# BCK_REVA_3.net
KiCad netlist of a schematic drawn in Altium Designer
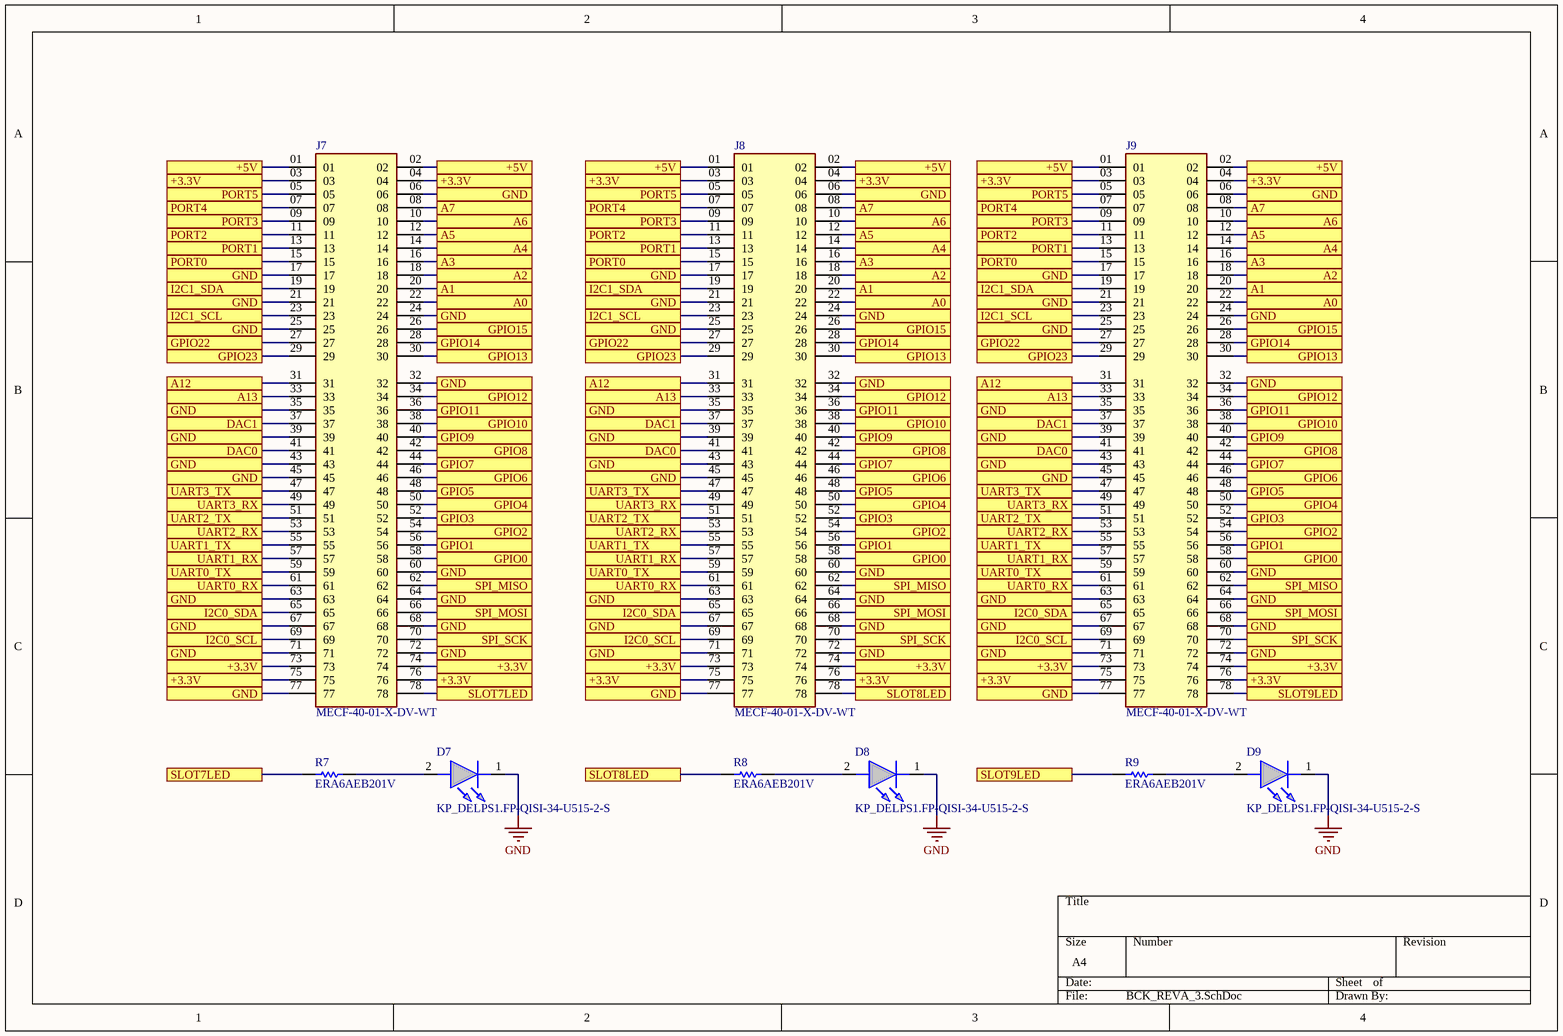
[diagram p0: BCK_REVA_3.SchDoc]

(export (version "E")
  (design (tool "Eeschema 10.0.6"))
  (components
    (comp (ref "D7")
      (value "KP_DELPS1.FP-QISI-34-U515-2-S")
      (footprint "KPDELPS1FPQISI34U5152S:KPDELPS1FPQISI34U5152S")
      (description "High Power LEDs - Single Color Pure Green TOPLED E1608")
      (fields
        (field (name "MANUFACTURER_PART_NUMBER") "KP DELPS1.FP-QISI-34-U515-2-S")
        (field (name "MOUSER PART NUMBER") "720-KPDELPS1FPA0817")
      )
      (libsource (lib "Backplane_REVA") (part "KP_DELPS1.FP-QISI-34-U515-2-S"))
    )
    (comp (ref "D8")
      (value "KP_DELPS1.FP-QISI-34-U515-2-S")
      (footprint "KPDELPS1FPQISI34U5152S:KPDELPS1FPQISI34U5152S")
      (description "High Power LEDs - Single Color Pure Green TOPLED E1608")
      (fields
        (field (name "MANUFACTURER_PART_NUMBER") "KP DELPS1.FP-QISI-34-U515-2-S")
        (field (name "MOUSER PART NUMBER") "720-KPDELPS1FPA0817")
      )
      (libsource (lib "Backplane_REVA") (part "KP_DELPS1.FP-QISI-34-U515-2-S"))
    )
    (comp (ref "D9")
      (value "KP_DELPS1.FP-QISI-34-U515-2-S")
      (footprint "KPDELPS1FPQISI34U5152S:KPDELPS1FPQISI34U5152S")
      (description "High Power LEDs - Single Color Pure Green TOPLED E1608")
      (fields
        (field (name "MANUFACTURER_PART_NUMBER") "KP DELPS1.FP-QISI-34-U515-2-S")
        (field (name "MOUSER PART NUMBER") "720-KPDELPS1FPA0817")
      )
      (libsource (lib "Backplane_REVA") (part "KP_DELPS1.FP-QISI-34-U515-2-S"))
    )
    (comp (ref "J7")
      (value "MECF-40-01-X-DV-WT")
      (footprint "SAMTEC_MECF-40-01-X-DV-WT:SAMTEC_MECF-40-01-X-DV-WT")
      (description "MECF .050\" EDGE CARD ASSEMBLY")
      (fields (field (name "MF") "Samtec"))
      (libsource (lib "Backplane_REVA") (part "MECF-40-01-X-DV-WT"))
    )
    (comp (ref "J8")
      (value "MECF-40-01-X-DV-WT")
      (footprint "SAMTEC_MECF-40-01-X-DV-WT:SAMTEC_MECF-40-01-X-DV-WT")
      (description "MECF .050\" EDGE CARD ASSEMBLY")
      (fields (field (name "MF") "Samtec"))
      (libsource (lib "Backplane_REVA") (part "MECF-40-01-X-DV-WT"))
    )
    (comp (ref "J9")
      (value "MECF-40-01-X-DV-WT")
      (footprint "SAMTEC_MECF-40-01-X-DV-WT:SAMTEC_MECF-40-01-X-DV-WT")
      (description "MECF .050\" EDGE CARD ASSEMBLY")
      (fields (field (name "MF") "Samtec"))
      (libsource (lib "Backplane_REVA") (part "MECF-40-01-X-DV-WT"))
    )
    (comp (ref "R7")
      (value "ERA6AEB201V")
      (footprint "RESC2013X60X40NL20T25")
      (fields (field (name "MANUFACTURER") "Panasonic"))
      (libsource (lib "Altium Content Vault") (part "RES"))
    )
    (comp (ref "R8")
      (value "ERA6AEB201V")
      (footprint "RESC2013X60X40NL20T25")
      (fields (field (name "MANUFACTURER") "Panasonic"))
      (libsource (lib "Altium Content Vault") (part "RES"))
    )
    (comp (ref "R9")
      (value "ERA6AEB201V")
      (footprint "RESC2013X60X40NL20T25")
      (fields (field (name "MANUFACTURER") "Panasonic"))
      (libsource (lib "Altium Content Vault") (part "RES"))
    )
  )
  (nets
    (net (code "1") (name "/+3.3V") (class "Default")
      (node (ref "J7") (pin "03") (pinfunction "03_03") (pintype "passive"))
      (node (ref "J7") (pin "04") (pinfunction "04_04") (pintype "passive"))
      (node (ref "J7") (pin "73") (pinfunction "73_73") (pintype "passive"))
      (node (ref "J7") (pin "74") (pinfunction "74_74") (pintype "passive"))
      (node (ref "J7") (pin "75") (pinfunction "75_75") (pintype "passive"))
      (node (ref "J7") (pin "76") (pinfunction "76_76") (pintype "passive"))
      (node (ref "J8") (pin "03") (pinfunction "03_03") (pintype "passive"))
      (node (ref "J8") (pin "04") (pinfunction "04_04") (pintype "passive"))
      (node (ref "J8") (pin "73") (pinfunction "73_73") (pintype "passive"))
      (node (ref "J8") (pin "74") (pinfunction "74_74") (pintype "passive"))
      (node (ref "J8") (pin "75") (pinfunction "75_75") (pintype "passive"))
      (node (ref "J8") (pin "76") (pinfunction "76_76") (pintype "passive"))
      (node (ref "J9") (pin "03") (pinfunction "03_03") (pintype "passive"))
      (node (ref "J9") (pin "04") (pinfunction "04_04") (pintype "passive"))
      (node (ref "J9") (pin "73") (pinfunction "73_73") (pintype "passive"))
      (node (ref "J9") (pin "74") (pinfunction "74_74") (pintype "passive"))
      (node (ref "J9") (pin "75") (pinfunction "75_75") (pintype "passive"))
      (node (ref "J9") (pin "76") (pinfunction "76_76") (pintype "passive"))
    )
    (net (code "2") (name "/+5V") (class "Default")
      (node (ref "J7") (pin "01") (pinfunction "01_01") (pintype "passive"))
      (node (ref "J7") (pin "02") (pinfunction "02_02") (pintype "passive"))
      (node (ref "J8") (pin "01") (pinfunction "01_01") (pintype "passive"))
      (node (ref "J8") (pin "02") (pinfunction "02_02") (pintype "passive"))
      (node (ref "J9") (pin "01") (pinfunction "01_01") (pintype "passive"))
      (node (ref "J9") (pin "02") (pinfunction "02_02") (pintype "passive"))
    )
    (net (code "3") (name "/A0") (class "Default")
      (node (ref "J7") (pin "22") (pinfunction "22_22") (pintype "passive"))
      (node (ref "J8") (pin "22") (pinfunction "22_22") (pintype "passive"))
      (node (ref "J9") (pin "22") (pinfunction "22_22") (pintype "passive"))
    )
    (net (code "4") (name "/A1") (class "Default")
      (node (ref "J7") (pin "20") (pinfunction "20_20") (pintype "passive"))
      (node (ref "J8") (pin "20") (pinfunction "20_20") (pintype "passive"))
      (node (ref "J9") (pin "20") (pinfunction "20_20") (pintype "passive"))
    )
    (net (code "5") (name "/A2") (class "Default")
      (node (ref "J7") (pin "18") (pinfunction "18_18") (pintype "passive"))
      (node (ref "J8") (pin "18") (pinfunction "18_18") (pintype "passive"))
      (node (ref "J9") (pin "18") (pinfunction "18_18") (pintype "passive"))
    )
    (net (code "6") (name "/A3") (class "Default")
      (node (ref "J7") (pin "16") (pinfunction "16_16") (pintype "passive"))
      (node (ref "J8") (pin "16") (pinfunction "16_16") (pintype "passive"))
      (node (ref "J9") (pin "16") (pinfunction "16_16") (pintype "passive"))
    )
    (net (code "7") (name "/A4") (class "Default")
      (node (ref "J7") (pin "14") (pinfunction "14_14") (pintype "passive"))
      (node (ref "J8") (pin "14") (pinfunction "14_14") (pintype "passive"))
      (node (ref "J9") (pin "14") (pinfunction "14_14") (pintype "passive"))
    )
    (net (code "8") (name "/A5") (class "Default")
      (node (ref "J7") (pin "12") (pinfunction "12_12") (pintype "passive"))
      (node (ref "J8") (pin "12") (pinfunction "12_12") (pintype "passive"))
      (node (ref "J9") (pin "12") (pinfunction "12_12") (pintype "passive"))
    )
    (net (code "9") (name "/A6") (class "Default")
      (node (ref "J7") (pin "10") (pinfunction "10_10") (pintype "passive"))
      (node (ref "J8") (pin "10") (pinfunction "10_10") (pintype "passive"))
      (node (ref "J9") (pin "10") (pinfunction "10_10") (pintype "passive"))
    )
    (net (code "10") (name "/A7") (class "Default")
      (node (ref "J7") (pin "08") (pinfunction "08_08") (pintype "passive"))
      (node (ref "J8") (pin "08") (pinfunction "08_08") (pintype "passive"))
      (node (ref "J9") (pin "08") (pinfunction "08_08") (pintype "passive"))
    )
    (net (code "11") (name "/A12") (class "Default")
      (node (ref "J7") (pin "31") (pinfunction "31_31") (pintype "passive"))
      (node (ref "J8") (pin "31") (pinfunction "31_31") (pintype "passive"))
      (node (ref "J9") (pin "31") (pinfunction "31_31") (pintype "passive"))
    )
    (net (code "12") (name "/A13") (class "Default")
      (node (ref "J7") (pin "33") (pinfunction "33_33") (pintype "passive"))
      (node (ref "J8") (pin "33") (pinfunction "33_33") (pintype "passive"))
      (node (ref "J9") (pin "33") (pinfunction "33_33") (pintype "passive"))
    )
    (net (code "13") (name "/DAC0") (class "Default")
      (node (ref "J7") (pin "41") (pinfunction "41_41") (pintype "passive"))
      (node (ref "J8") (pin "41") (pinfunction "41_41") (pintype "passive"))
      (node (ref "J9") (pin "41") (pinfunction "41_41") (pintype "passive"))
    )
    (net (code "14") (name "/DAC1") (class "Default")
      (node (ref "J7") (pin "37") (pinfunction "37_37") (pintype "passive"))
      (node (ref "J8") (pin "37") (pinfunction "37_37") (pintype "passive"))
      (node (ref "J9") (pin "37") (pinfunction "37_37") (pintype "passive"))
    )
    (net (code "15") (name "/GPIO0") (class "Default")
      (node (ref "J7") (pin "58") (pinfunction "58_58") (pintype "passive"))
      (node (ref "J8") (pin "58") (pinfunction "58_58") (pintype "passive"))
      (node (ref "J9") (pin "58") (pinfunction "58_58") (pintype "passive"))
    )
    (net (code "16") (name "/GPIO1") (class "Default")
      (node (ref "J7") (pin "56") (pinfunction "56_56") (pintype "passive"))
      (node (ref "J8") (pin "56") (pinfunction "56_56") (pintype "passive"))
      (node (ref "J9") (pin "56") (pinfunction "56_56") (pintype "passive"))
    )
    (net (code "17") (name "/GPIO2") (class "Default")
      (node (ref "J7") (pin "54") (pinfunction "54_54") (pintype "passive"))
      (node (ref "J8") (pin "54") (pinfunction "54_54") (pintype "passive"))
      (node (ref "J9") (pin "54") (pinfunction "54_54") (pintype "passive"))
    )
    (net (code "18") (name "/GPIO3") (class "Default")
      (node (ref "J7") (pin "52") (pinfunction "52_52") (pintype "passive"))
      (node (ref "J8") (pin "52") (pinfunction "52_52") (pintype "passive"))
      (node (ref "J9") (pin "52") (pinfunction "52_52") (pintype "passive"))
    )
    (net (code "19") (name "/GPIO4") (class "Default")
      (node (ref "J7") (pin "50") (pinfunction "50_50") (pintype "passive"))
      (node (ref "J8") (pin "50") (pinfunction "50_50") (pintype "passive"))
      (node (ref "J9") (pin "50") (pinfunction "50_50") (pintype "passive"))
    )
    (net (code "20") (name "/GPIO5") (class "Default")
      (node (ref "J7") (pin "48") (pinfunction "48_48") (pintype "passive"))
      (node (ref "J8") (pin "48") (pinfunction "48_48") (pintype "passive"))
      (node (ref "J9") (pin "48") (pinfunction "48_48") (pintype "passive"))
    )
    (net (code "21") (name "/GPIO6") (class "Default")
      (node (ref "J7") (pin "46") (pinfunction "46_46") (pintype "passive"))
      (node (ref "J8") (pin "46") (pinfunction "46_46") (pintype "passive"))
      (node (ref "J9") (pin "46") (pinfunction "46_46") (pintype "passive"))
    )
    (net (code "22") (name "/GPIO7") (class "Default")
      (node (ref "J7") (pin "44") (pinfunction "44_44") (pintype "passive"))
      (node (ref "J8") (pin "44") (pinfunction "44_44") (pintype "passive"))
      (node (ref "J9") (pin "44") (pinfunction "44_44") (pintype "passive"))
    )
    (net (code "23") (name "/GPIO8") (class "Default")
      (node (ref "J7") (pin "42") (pinfunction "42_42") (pintype "passive"))
      (node (ref "J8") (pin "42") (pinfunction "42_42") (pintype "passive"))
      (node (ref "J9") (pin "42") (pinfunction "42_42") (pintype "passive"))
    )
    (net (code "24") (name "/GPIO9") (class "Default")
      (node (ref "J7") (pin "40") (pinfunction "40_40") (pintype "passive"))
      (node (ref "J8") (pin "40") (pinfunction "40_40") (pintype "passive"))
      (node (ref "J9") (pin "40") (pinfunction "40_40") (pintype "passive"))
    )
    (net (code "25") (name "/GPIO10") (class "Default")
      (node (ref "J7") (pin "38") (pinfunction "38_38") (pintype "passive"))
      (node (ref "J8") (pin "38") (pinfunction "38_38") (pintype "passive"))
      (node (ref "J9") (pin "38") (pinfunction "38_38") (pintype "passive"))
    )
    (net (code "26") (name "/GPIO11") (class "Default")
      (node (ref "J7") (pin "36") (pinfunction "36_36") (pintype "passive"))
      (node (ref "J8") (pin "36") (pinfunction "36_36") (pintype "passive"))
      (node (ref "J9") (pin "36") (pinfunction "36_36") (pintype "passive"))
    )
    (net (code "27") (name "/GPIO12") (class "Default")
      (node (ref "J7") (pin "34") (pinfunction "34_34") (pintype "passive"))
      (node (ref "J8") (pin "34") (pinfunction "34_34") (pintype "passive"))
      (node (ref "J9") (pin "34") (pinfunction "34_34") (pintype "passive"))
    )
    (net (code "28") (name "/GPIO13") (class "Default")
      (node (ref "J7") (pin "30") (pinfunction "30_30") (pintype "passive"))
      (node (ref "J8") (pin "30") (pinfunction "30_30") (pintype "passive"))
      (node (ref "J9") (pin "30") (pinfunction "30_30") (pintype "passive"))
    )
    (net (code "29") (name "/GPIO14") (class "Default")
      (node (ref "J7") (pin "28") (pinfunction "28_28") (pintype "passive"))
      (node (ref "J8") (pin "28") (pinfunction "28_28") (pintype "passive"))
      (node (ref "J9") (pin "28") (pinfunction "28_28") (pintype "passive"))
    )
    (net (code "30") (name "/GPIO15") (class "Default")
      (node (ref "J7") (pin "26") (pinfunction "26_26") (pintype "passive"))
      (node (ref "J8") (pin "26") (pinfunction "26_26") (pintype "passive"))
      (node (ref "J9") (pin "26") (pinfunction "26_26") (pintype "passive"))
    )
    (net (code "31") (name "/GPIO22") (class "Default")
      (node (ref "J7") (pin "27") (pinfunction "27_27") (pintype "passive"))
      (node (ref "J8") (pin "27") (pinfunction "27_27") (pintype "passive"))
      (node (ref "J9") (pin "27") (pinfunction "27_27") (pintype "passive"))
    )
    (net (code "32") (name "/GPIO23") (class "Default")
      (node (ref "J7") (pin "29") (pinfunction "29_29") (pintype "passive"))
      (node (ref "J8") (pin "29") (pinfunction "29_29") (pintype "passive"))
      (node (ref "J9") (pin "29") (pinfunction "29_29") (pintype "passive"))
    )
    (net (code "33") (name "/I2C0_SCL") (class "Default")
      (node (ref "J7") (pin "69") (pinfunction "69_69") (pintype "passive"))
      (node (ref "J8") (pin "69") (pinfunction "69_69") (pintype "passive"))
      (node (ref "J9") (pin "69") (pinfunction "69_69") (pintype "passive"))
    )
    (net (code "34") (name "/I2C0_SDA") (class "Default")
      (node (ref "J7") (pin "65") (pinfunction "65_65") (pintype "passive"))
      (node (ref "J8") (pin "65") (pinfunction "65_65") (pintype "passive"))
      (node (ref "J9") (pin "65") (pinfunction "65_65") (pintype "passive"))
    )
    (net (code "35") (name "/I2C1_SCL") (class "Default")
      (node (ref "J7") (pin "23") (pinfunction "23_23") (pintype "passive"))
      (node (ref "J8") (pin "23") (pinfunction "23_23") (pintype "passive"))
      (node (ref "J9") (pin "23") (pinfunction "23_23") (pintype "passive"))
    )
    (net (code "36") (name "/I2C1_SDA") (class "Default")
      (node (ref "J7") (pin "19") (pinfunction "19_19") (pintype "passive"))
      (node (ref "J8") (pin "19") (pinfunction "19_19") (pintype "passive"))
      (node (ref "J9") (pin "19") (pinfunction "19_19") (pintype "passive"))
    )
    (net (code "37") (name "/PORT0") (class "Default")
      (node (ref "J7") (pin "15") (pinfunction "15_15") (pintype "passive"))
      (node (ref "J8") (pin "15") (pinfunction "15_15") (pintype "passive"))
      (node (ref "J9") (pin "15") (pinfunction "15_15") (pintype "passive"))
    )
    (net (code "38") (name "/PORT1") (class "Default")
      (node (ref "J7") (pin "13") (pinfunction "13_13") (pintype "passive"))
      (node (ref "J8") (pin "13") (pinfunction "13_13") (pintype "passive"))
      (node (ref "J9") (pin "13") (pinfunction "13_13") (pintype "passive"))
    )
    (net (code "39") (name "/PORT2") (class "Default")
      (node (ref "J7") (pin "11") (pinfunction "11_11") (pintype "passive"))
      (node (ref "J8") (pin "11") (pinfunction "11_11") (pintype "passive"))
      (node (ref "J9") (pin "11") (pinfunction "11_11") (pintype "passive"))
    )
    (net (code "40") (name "/PORT3") (class "Default")
      (node (ref "J7") (pin "09") (pinfunction "09_09") (pintype "passive"))
      (node (ref "J8") (pin "09") (pinfunction "09_09") (pintype "passive"))
      (node (ref "J9") (pin "09") (pinfunction "09_09") (pintype "passive"))
    )
    (net (code "41") (name "/PORT4") (class "Default")
      (node (ref "J7") (pin "07") (pinfunction "07_07") (pintype "passive"))
      (node (ref "J8") (pin "07") (pinfunction "07_07") (pintype "passive"))
      (node (ref "J9") (pin "07") (pinfunction "07_07") (pintype "passive"))
    )
    (net (code "42") (name "/PORT5") (class "Default")
      (node (ref "J7") (pin "05") (pinfunction "05_05") (pintype "passive"))
      (node (ref "J8") (pin "05") (pinfunction "05_05") (pintype "passive"))
      (node (ref "J9") (pin "05") (pinfunction "05_05") (pintype "passive"))
    )
    (net (code "43") (name "/SLOT7LED") (class "Default")
      (node (ref "J7") (pin "78") (pinfunction "78_78") (pintype "passive"))
      (node (ref "R7") (pin "1") (pinfunction "1_1") (pintype "passive"))
    )
    (net (code "44") (name "/SLOT8LED") (class "Default")
      (node (ref "J8") (pin "78") (pinfunction "78_78") (pintype "passive"))
      (node (ref "R8") (pin "1") (pinfunction "1_1") (pintype "passive"))
    )
    (net (code "45") (name "/SLOT9LED") (class "Default")
      (node (ref "J9") (pin "78") (pinfunction "78_78") (pintype "passive"))
      (node (ref "R9") (pin "1") (pinfunction "1_1") (pintype "passive"))
    )
    (net (code "46") (name "/SPI_MISO") (class "Default")
      (node (ref "J7") (pin "62") (pinfunction "62_62") (pintype "passive"))
      (node (ref "J8") (pin "62") (pinfunction "62_62") (pintype "passive"))
      (node (ref "J9") (pin "62") (pinfunction "62_62") (pintype "passive"))
    )
    (net (code "47") (name "/SPI_MOSI") (class "Default")
      (node (ref "J7") (pin "66") (pinfunction "66_66") (pintype "passive"))
      (node (ref "J8") (pin "66") (pinfunction "66_66") (pintype "passive"))
      (node (ref "J9") (pin "66") (pinfunction "66_66") (pintype "passive"))
    )
    (net (code "48") (name "/SPI_SCK") (class "Default")
      (node (ref "J7") (pin "70") (pinfunction "70_70") (pintype "passive"))
      (node (ref "J8") (pin "70") (pinfunction "70_70") (pintype "passive"))
      (node (ref "J9") (pin "70") (pinfunction "70_70") (pintype "passive"))
    )
    (net (code "49") (name "/UART0_RX") (class "Default")
      (node (ref "J7") (pin "61") (pinfunction "61_61") (pintype "passive"))
      (node (ref "J8") (pin "61") (pinfunction "61_61") (pintype "passive"))
      (node (ref "J9") (pin "61") (pinfunction "61_61") (pintype "passive"))
    )
    (net (code "50") (name "/UART0_TX") (class "Default")
      (node (ref "J7") (pin "59") (pinfunction "59_59") (pintype "passive"))
      (node (ref "J8") (pin "59") (pinfunction "59_59") (pintype "passive"))
      (node (ref "J9") (pin "59") (pinfunction "59_59") (pintype "passive"))
    )
    (net (code "51") (name "/UART1_RX") (class "Default")
      (node (ref "J7") (pin "57") (pinfunction "57_57") (pintype "passive"))
      (node (ref "J8") (pin "57") (pinfunction "57_57") (pintype "passive"))
      (node (ref "J9") (pin "57") (pinfunction "57_57") (pintype "passive"))
    )
    (net (code "52") (name "/UART1_TX") (class "Default")
      (node (ref "J7") (pin "55") (pinfunction "55_55") (pintype "passive"))
      (node (ref "J8") (pin "55") (pinfunction "55_55") (pintype "passive"))
      (node (ref "J9") (pin "55") (pinfunction "55_55") (pintype "passive"))
    )
    (net (code "53") (name "/UART2_RX") (class "Default")
      (node (ref "J7") (pin "53") (pinfunction "53_53") (pintype "passive"))
      (node (ref "J8") (pin "53") (pinfunction "53_53") (pintype "passive"))
      (node (ref "J9") (pin "53") (pinfunction "53_53") (pintype "passive"))
    )
    (net (code "54") (name "/UART2_TX") (class "Default")
      (node (ref "J7") (pin "51") (pinfunction "51_51") (pintype "passive"))
      (node (ref "J8") (pin "51") (pinfunction "51_51") (pintype "passive"))
      (node (ref "J9") (pin "51") (pinfunction "51_51") (pintype "passive"))
    )
    (net (code "55") (name "/UART3_RX") (class "Default")
      (node (ref "J7") (pin "49") (pinfunction "49_49") (pintype "passive"))
      (node (ref "J8") (pin "49") (pinfunction "49_49") (pintype "passive"))
      (node (ref "J9") (pin "49") (pinfunction "49_49") (pintype "passive"))
    )
    (net (code "56") (name "/UART3_TX") (class "Default")
      (node (ref "J7") (pin "47") (pinfunction "47_47") (pintype "passive"))
      (node (ref "J8") (pin "47") (pinfunction "47_47") (pintype "passive"))
      (node (ref "J9") (pin "47") (pinfunction "47_47") (pintype "passive"))
    )
    (net (code "57") (name "GND") (class "Default")
      (node (ref "D7") (pin "1") (pinfunction "K_1") (pintype "passive"))
      (node (ref "D8") (pin "1") (pinfunction "K_1") (pintype "passive"))
      (node (ref "D9") (pin "1") (pinfunction "K_1") (pintype "passive"))
      (node (ref "J7") (pin "06") (pinfunction "06_06") (pintype "passive"))
      (node (ref "J7") (pin "17") (pinfunction "17_17") (pintype "passive"))
      (node (ref "J7") (pin "21") (pinfunction "21_21") (pintype "passive"))
      (node (ref "J7") (pin "24") (pinfunction "24_24") (pintype "passive"))
      (node (ref "J7") (pin "25") (pinfunction "25_25") (pintype "passive"))
      (node (ref "J7") (pin "32") (pinfunction "32_32") (pintype "passive"))
      (node (ref "J7") (pin "35") (pinfunction "35_35") (pintype "passive"))
      (node (ref "J7") (pin "39") (pinfunction "39_39") (pintype "passive"))
      (node (ref "J7") (pin "43") (pinfunction "43_43") (pintype "passive"))
      (node (ref "J7") (pin "45") (pinfunction "45_45") (pintype "passive"))
      (node (ref "J7") (pin "60") (pinfunction "60_60") (pintype "passive"))
      (node (ref "J7") (pin "63") (pinfunction "63_63") (pintype "passive"))
      (node (ref "J7") (pin "64") (pinfunction "64_64") (pintype "passive"))
      (node (ref "J7") (pin "67") (pinfunction "67_67") (pintype "passive"))
      (node (ref "J7") (pin "68") (pinfunction "68_68") (pintype "passive"))
      (node (ref "J7") (pin "71") (pinfunction "71_71") (pintype "passive"))
      (node (ref "J7") (pin "72") (pinfunction "72_72") (pintype "passive"))
      (node (ref "J7") (pin "77") (pinfunction "77_77") (pintype "passive"))
      (node (ref "J8") (pin "06") (pinfunction "06_06") (pintype "passive"))
      (node (ref "J8") (pin "17") (pinfunction "17_17") (pintype "passive"))
      (node (ref "J8") (pin "21") (pinfunction "21_21") (pintype "passive"))
      (node (ref "J8") (pin "24") (pinfunction "24_24") (pintype "passive"))
      (node (ref "J8") (pin "25") (pinfunction "25_25") (pintype "passive"))
      (node (ref "J8") (pin "32") (pinfunction "32_32") (pintype "passive"))
      (node (ref "J8") (pin "35") (pinfunction "35_35") (pintype "passive"))
      (node (ref "J8") (pin "39") (pinfunction "39_39") (pintype "passive"))
      (node (ref "J8") (pin "43") (pinfunction "43_43") (pintype "passive"))
      (node (ref "J8") (pin "45") (pinfunction "45_45") (pintype "passive"))
      (node (ref "J8") (pin "60") (pinfunction "60_60") (pintype "passive"))
      (node (ref "J8") (pin "63") (pinfunction "63_63") (pintype "passive"))
      (node (ref "J8") (pin "64") (pinfunction "64_64") (pintype "passive"))
      (node (ref "J8") (pin "67") (pinfunction "67_67") (pintype "passive"))
      (node (ref "J8") (pin "68") (pinfunction "68_68") (pintype "passive"))
      (node (ref "J8") (pin "71") (pinfunction "71_71") (pintype "passive"))
      (node (ref "J8") (pin "72") (pinfunction "72_72") (pintype "passive"))
      (node (ref "J8") (pin "77") (pinfunction "77_77") (pintype "passive"))
      (node (ref "J9") (pin "06") (pinfunction "06_06") (pintype "passive"))
      (node (ref "J9") (pin "17") (pinfunction "17_17") (pintype "passive"))
      (node (ref "J9") (pin "21") (pinfunction "21_21") (pintype "passive"))
      (node (ref "J9") (pin "24") (pinfunction "24_24") (pintype "passive"))
      (node (ref "J9") (pin "25") (pinfunction "25_25") (pintype "passive"))
      (node (ref "J9") (pin "32") (pinfunction "32_32") (pintype "passive"))
      (node (ref "J9") (pin "35") (pinfunction "35_35") (pintype "passive"))
      (node (ref "J9") (pin "39") (pinfunction "39_39") (pintype "passive"))
      (node (ref "J9") (pin "43") (pinfunction "43_43") (pintype "passive"))
      (node (ref "J9") (pin "45") (pinfunction "45_45") (pintype "passive"))
      (node (ref "J9") (pin "60") (pinfunction "60_60") (pintype "passive"))
      (node (ref "J9") (pin "63") (pinfunction "63_63") (pintype "passive"))
      (node (ref "J9") (pin "64") (pinfunction "64_64") (pintype "passive"))
      (node (ref "J9") (pin "67") (pinfunction "67_67") (pintype "passive"))
      (node (ref "J9") (pin "68") (pinfunction "68_68") (pintype "passive"))
      (node (ref "J9") (pin "71") (pinfunction "71_71") (pintype "passive"))
      (node (ref "J9") (pin "72") (pinfunction "72_72") (pintype "passive"))
      (node (ref "J9") (pin "77") (pinfunction "77_77") (pintype "passive"))
    )
    (net (code "58") (name "Net-(D7-A)") (class "Default")
      (node (ref "D7") (pin "2") (pinfunction "A_2") (pintype "passive"))
      (node (ref "R7") (pin "2") (pinfunction "2_2") (pintype "passive"))
    )
    (net (code "59") (name "Net-(D8-A)") (class "Default")
      (node (ref "D8") (pin "2") (pinfunction "A_2") (pintype "passive"))
      (node (ref "R8") (pin "2") (pinfunction "2_2") (pintype "passive"))
    )
    (net (code "60") (name "Net-(D9-A)") (class "Default")
      (node (ref "D9") (pin "2") (pinfunction "A_2") (pintype "passive"))
      (node (ref "R9") (pin "2") (pinfunction "2_2") (pintype "passive"))
    )
  )
)
